# Cartucho_Sin_Led.net
KiCad netlist of a schematic drawn in EAGLE
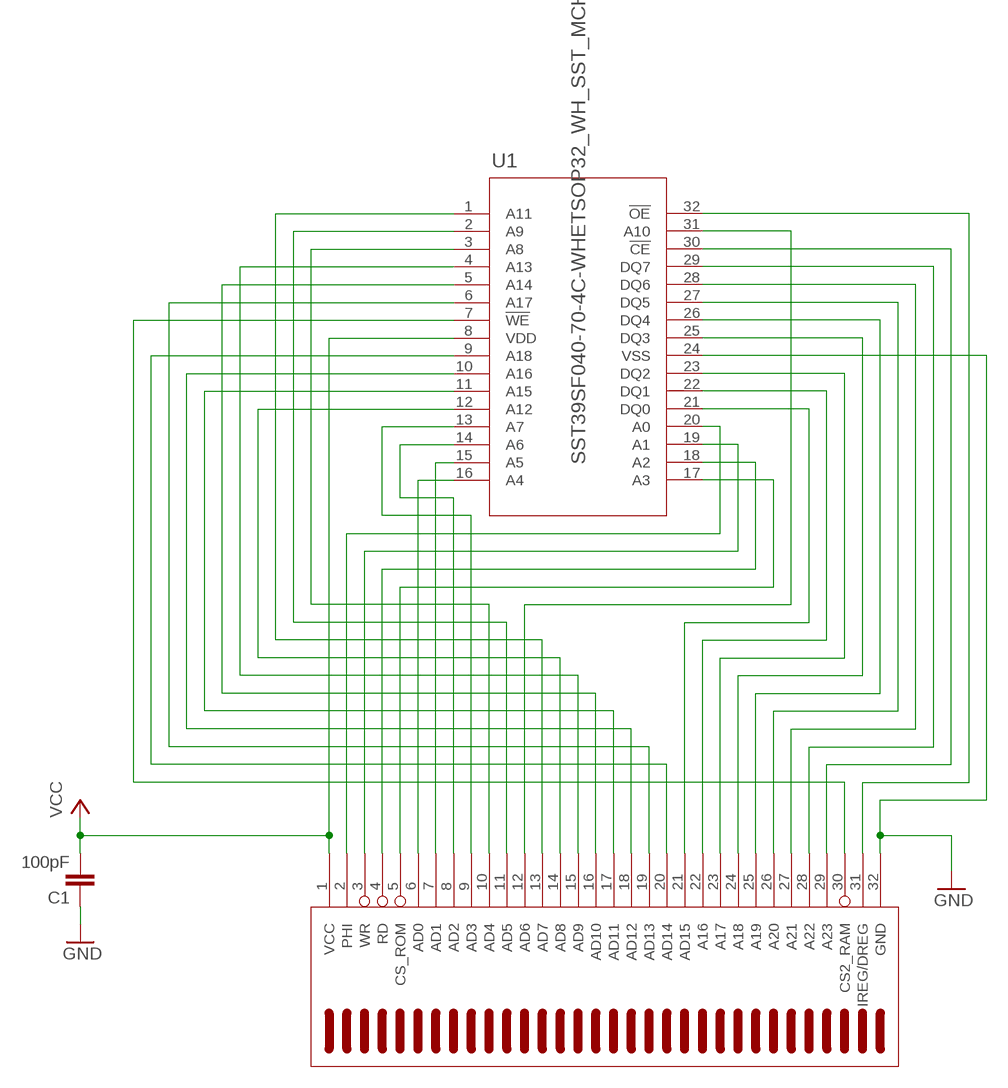
[diagram p0: schematic, sheet 1]

(export (version "E")
  (design (tool "Eeschema 10.0.6"))
  (components
    (comp (ref "C1")
      (value "100pF")
      (footprint "eagle-import:C0805")
      (libsource (lib "eagle-import") (part "C-EUC0805"))
    )
    (comp (ref "U$1")
      (value "GBA_CARTNORMAL")
      (footprint "eagle-import:GBA_CART")
      (libsource (lib "eagle-import") (part "GBA_CARTNORMAL"))
    )
    (comp (ref "U1")
      (value "SST39SF040-70-4C-WHETSOP32_WH_SST_MCH-M")
      (footprint "eagle-import:TSOP32_WH_SST_MCH-M")
      (fields
        (field (name "MANUFACTURER_PART_NUMBER") "SST39SF040-70-4C-WHE")
        (field (name "COPYRIGHT") "Copyright (C) 2018 Accelerated Designs. All rights reserved")
      )
      (libsource (lib "eagle-import") (part "SST39SF040-70-4C-WHETSOP32_WH_SST_MCH-M"))
    )
  )
  (nets
    (net (code "1") (name "GND") (class "Default")
      (node (ref "C1") (pin "1") (pinfunction "1_1") (pintype "passive"))
      (node (ref "U$1") (pin "32") (pinfunction "GND_32") (pintype "power_in"))
      (node (ref "U1") (pin "24") (pinfunction "VSS_24") (pintype "power_in"))
    )
    (net (code "2") (name "Net-(U$1-A16)") (class "Default")
      (node (ref "U$1") (pin "22") (pinfunction "A16_22") (pintype "output"))
      (node (ref "U1") (pin "22") (pinfunction "DQ1_22") (pintype "bidirectional"))
    )
    (net (code "3") (name "Net-(U$1-A17)") (class "Default")
      (node (ref "U$1") (pin "23") (pinfunction "A17_23") (pintype "output"))
      (node (ref "U1") (pin "23") (pinfunction "DQ2_23") (pintype "bidirectional"))
    )
    (net (code "4") (name "Net-(U$1-A18)") (class "Default")
      (node (ref "U$1") (pin "24") (pinfunction "A18_24") (pintype "output"))
      (node (ref "U1") (pin "25") (pinfunction "DQ3_25") (pintype "bidirectional"))
    )
    (net (code "5") (name "Net-(U$1-A19)") (class "Default")
      (node (ref "U$1") (pin "25") (pinfunction "A19_25") (pintype "output"))
      (node (ref "U1") (pin "26") (pinfunction "DQ4_26") (pintype "bidirectional"))
    )
    (net (code "6") (name "Net-(U$1-A20)") (class "Default")
      (node (ref "U$1") (pin "26") (pinfunction "A20_26") (pintype "output"))
      (node (ref "U1") (pin "27") (pinfunction "DQ5_27") (pintype "bidirectional"))
    )
    (net (code "7") (name "Net-(U$1-A21)") (class "Default")
      (node (ref "U$1") (pin "27") (pinfunction "A21_27") (pintype "output"))
      (node (ref "U1") (pin "28") (pinfunction "DQ6_28") (pintype "bidirectional"))
    )
    (net (code "8") (name "Net-(U$1-A22)") (class "Default")
      (node (ref "U$1") (pin "28") (pinfunction "A22_28") (pintype "output"))
      (node (ref "U1") (pin "29") (pinfunction "DQ7_29") (pintype "bidirectional"))
    )
    (net (code "9") (name "Net-(U$1-A23)") (class "Default")
      (node (ref "U$1") (pin "29") (pinfunction "A23_29") (pintype "output"))
      (node (ref "U1") (pin "30") (pinfunction "~{CE}_30") (pintype "passive"))
    )
    (net (code "10") (name "Net-(U$1-AD0)") (class "Default")
      (node (ref "U$1") (pin "6") (pinfunction "AD0_6") (pintype "bidirectional"))
      (node (ref "U1") (pin "16") (pinfunction "A4_16") (pintype "input"))
    )
    (net (code "11") (name "Net-(U$1-AD1)") (class "Default")
      (node (ref "U$1") (pin "7") (pinfunction "AD1_7") (pintype "bidirectional"))
      (node (ref "U1") (pin "15") (pinfunction "A5_15") (pintype "input"))
    )
    (net (code "12") (name "Net-(U$1-AD2)") (class "Default")
      (node (ref "U$1") (pin "8") (pinfunction "AD2_8") (pintype "bidirectional"))
      (node (ref "U1") (pin "14") (pinfunction "A6_14") (pintype "input"))
    )
    (net (code "13") (name "Net-(U$1-AD3)") (class "Default")
      (node (ref "U$1") (pin "9") (pinfunction "AD3_9") (pintype "bidirectional"))
      (node (ref "U1") (pin "13") (pinfunction "A7_13") (pintype "input"))
    )
    (net (code "14") (name "Net-(U$1-AD4)") (class "Default")
      (node (ref "U$1") (pin "10") (pinfunction "AD4_10") (pintype "bidirectional"))
      (node (ref "U1") (pin "3") (pinfunction "A8_3") (pintype "input"))
    )
    (net (code "15") (name "Net-(U$1-AD5)") (class "Default")
      (node (ref "U$1") (pin "11") (pinfunction "AD5_11") (pintype "bidirectional"))
      (node (ref "U1") (pin "2") (pinfunction "A9_2") (pintype "input"))
    )
    (net (code "16") (name "Net-(U$1-AD6)") (class "Default")
      (node (ref "U$1") (pin "12") (pinfunction "AD6_12") (pintype "bidirectional"))
      (node (ref "U1") (pin "31") (pinfunction "A10_31") (pintype "input"))
    )
    (net (code "17") (name "Net-(U$1-AD7)") (class "Default")
      (node (ref "U$1") (pin "13") (pinfunction "AD7_13") (pintype "bidirectional"))
      (node (ref "U1") (pin "1") (pinfunction "A11_1") (pintype "input"))
    )
    (net (code "18") (name "Net-(U$1-AD8)") (class "Default")
      (node (ref "U$1") (pin "14") (pinfunction "AD8_14") (pintype "bidirectional"))
      (node (ref "U1") (pin "12") (pinfunction "A12_12") (pintype "input"))
    )
    (net (code "19") (name "Net-(U$1-AD9)") (class "Default")
      (node (ref "U$1") (pin "15") (pinfunction "AD9_15") (pintype "bidirectional"))
      (node (ref "U1") (pin "4") (pinfunction "A13_4") (pintype "input"))
    )
    (net (code "20") (name "Net-(U$1-AD10)") (class "Default")
      (node (ref "U$1") (pin "16") (pinfunction "AD10_16") (pintype "bidirectional"))
      (node (ref "U1") (pin "5") (pinfunction "A14_5") (pintype "input"))
    )
    (net (code "21") (name "Net-(U$1-AD11)") (class "Default")
      (node (ref "U$1") (pin "17") (pinfunction "AD11_17") (pintype "bidirectional"))
      (node (ref "U1") (pin "11") (pinfunction "A15_11") (pintype "input"))
    )
    (net (code "22") (name "Net-(U$1-AD12)") (class "Default")
      (node (ref "U$1") (pin "18") (pinfunction "AD12_18") (pintype "bidirectional"))
      (node (ref "U1") (pin "10") (pinfunction "A16_10") (pintype "input"))
    )
    (net (code "23") (name "Net-(U$1-AD13)") (class "Default")
      (node (ref "U$1") (pin "19") (pinfunction "AD13_19") (pintype "bidirectional"))
      (node (ref "U1") (pin "6") (pinfunction "A17_6") (pintype "input"))
    )
    (net (code "24") (name "Net-(U$1-AD14)") (class "Default")
      (node (ref "U$1") (pin "20") (pinfunction "AD14_20") (pintype "bidirectional"))
      (node (ref "U1") (pin "9") (pinfunction "A18_9") (pintype "input"))
    )
    (net (code "25") (name "Net-(U$1-AD15)") (class "Default")
      (node (ref "U$1") (pin "21") (pinfunction "AD15_21") (pintype "bidirectional"))
      (node (ref "U1") (pin "21") (pinfunction "DQ0_21") (pintype "bidirectional"))
    )
    (net (code "26") (name "Net-(U$1-CS2_RAM)") (class "Default")
      (node (ref "U$1") (pin "30") (pinfunction "CS2_RAM_30") (pintype "output"))
      (node (ref "U1") (pin "7") (pinfunction "~{WE}_7") (pintype "passive"))
    )
    (net (code "27") (name "Net-(U$1-CS_ROM)") (class "Default")
      (node (ref "U$1") (pin "5") (pinfunction "CS_ROM_5") (pintype "output"))
      (node (ref "U1") (pin "17") (pinfunction "A3_17") (pintype "input"))
    )
    (net (code "28") (name "Net-(U$1-IREG{slash}DREG)") (class "Default")
      (node (ref "U$1") (pin "31") (pinfunction "IREG/DREG_31") (pintype "input"))
      (node (ref "U1") (pin "32") (pinfunction "~{OE}_32") (pintype "output"))
    )
    (net (code "29") (name "Net-(U$1-PHI)") (class "Default")
      (node (ref "U$1") (pin "2") (pinfunction "PHI_2") (pintype "bidirectional"))
      (node (ref "U1") (pin "20") (pinfunction "A0_20") (pintype "input"))
    )
    (net (code "30") (name "Net-(U$1-RD)") (class "Default")
      (node (ref "U$1") (pin "4") (pinfunction "RD_4") (pintype "output"))
      (node (ref "U1") (pin "18") (pinfunction "A2_18") (pintype "input"))
    )
    (net (code "31") (name "Net-(U$1-WR)") (class "Default")
      (node (ref "U$1") (pin "3") (pinfunction "WR_3") (pintype "output"))
      (node (ref "U1") (pin "19") (pinfunction "A1_19") (pintype "input"))
    )
    (net (code "32") (name "VCC") (class "Default")
      (node (ref "C1") (pin "2") (pinfunction "2_2") (pintype "passive"))
      (node (ref "U$1") (pin "1") (pinfunction "VCC_1") (pintype "power_in"))
      (node (ref "U1") (pin "8") (pinfunction "VDD_8") (pintype "power_in"))
    )
  )
)
